# Valmar.net
KiCad netlist of a schematic drawn in EasyEDA Pro
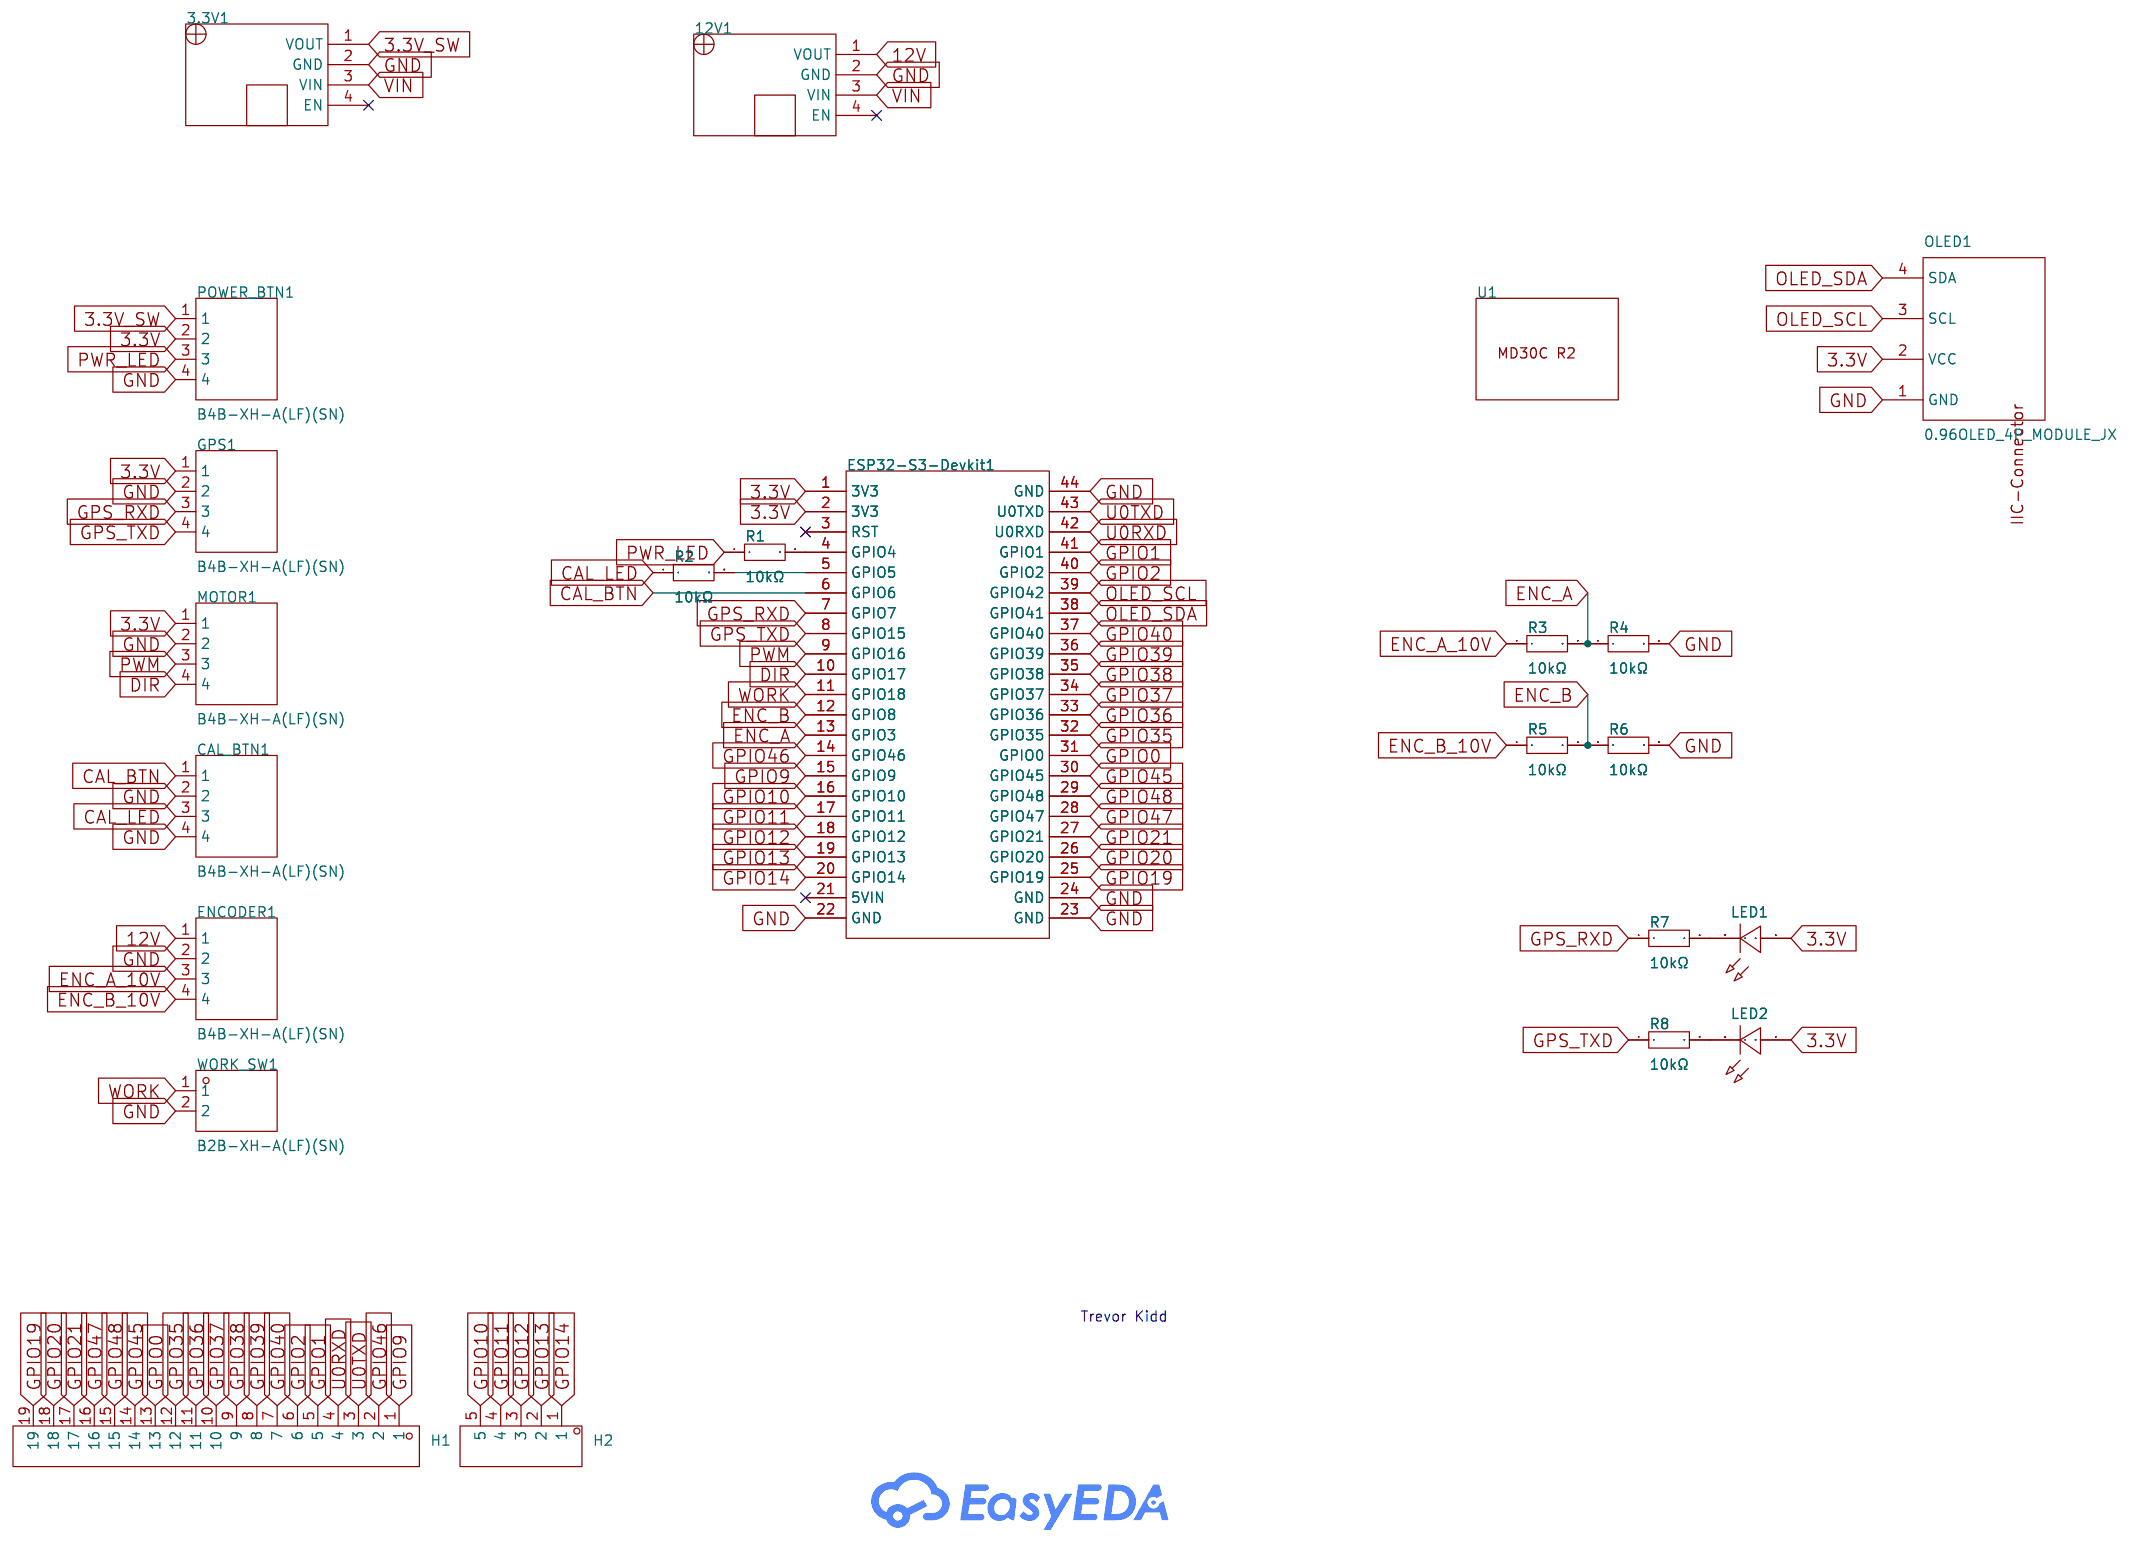
[diagram p0: schematic sheet]

(export (version "E")
  (design (tool "Eeschema 10.0.6"))
  (components
    (comp (ref "3.3V1")
      (value "~")
      (footprint "easyedapro:Power Module")
      (libsource (lib "easyedapro") (part "Power Module"))
    )
    (comp (ref "12V1")
      (value "~")
      (footprint "easyedapro:Power Module")
      (libsource (lib "easyedapro") (part "Power Module"))
    )
    (comp (ref "CAL_BTN1")
      (value "B4B-XH-A(LF)(SN)")
      (footprint "easyedapro:CONN-TH_B4B-XH-A-LF-SN")
      (fields (field (name "Manufacturer") "JST"))
      (libsource (lib "easyedapro") (part "B4B-XH-A(LF)(SN)"))
    )
    (comp (ref "ENCODER1")
      (value "B4B-XH-A(LF)(SN)")
      (footprint "easyedapro:CONN-TH_B4B-XH-A-LF-SN")
      (fields (field (name "Manufacturer") "JST"))
      (libsource (lib "easyedapro") (part "B4B-XH-A(LF)(SN)"))
    )
    (comp (ref "ESP32-S3-Devkit1")
      (value "~")
      (footprint "easyedapro:ESP32-S3-Devkit")
      (libsource (lib "easyedapro") (part "ESP32S3-Devkit"))
    )
    (comp (ref "GPS1")
      (value "B4B-XH-A(LF)(SN)")
      (footprint "easyedapro:CONN-TH_B4B-XH-A-LF-SN")
      (fields (field (name "Manufacturer") "JST"))
      (libsource (lib "easyedapro") (part "B4B-XH-A(LF)(SN)"))
    )
    (comp (ref "H1")
      (value "~")
      (footprint "easyedapro:HDR-TH_19P-P2.54-V-M")
      (libsource (lib "easyedapro") (part "HDR_2.54-1x19P"))
    )
    (comp (ref "H2")
      (value "~")
      (footprint "easyedapro:HDR-TH_5P-P2.54-V-M")
      (libsource (lib "easyedapro") (part "MTP125-1105S1"))
    )
    (comp (ref "LED1")
      (value "~")
      (footprint "easyedapro:LED-TH_BD3.8-P2.54-FD_BLUE")
      (libsource (lib "easyedapro") (part "LED_TH-B"))
    )
    (comp (ref "LED2")
      (value "~")
      (footprint "easyedapro:LED-TH_BD3.8-P2.54-FD_BLUE")
      (libsource (lib "easyedapro") (part "LED_TH-B"))
    )
    (comp (ref "MOTOR1")
      (value "B4B-XH-A(LF)(SN)")
      (footprint "easyedapro:CONN-TH_B4B-XH-A-LF-SN")
      (fields (field (name "Manufacturer") "JST"))
      (libsource (lib "easyedapro") (part "B4B-XH-A(LF)(SN)"))
    )
    (comp (ref "OLED1")
      (value "0.96OLED_4P_MODULE_JX")
      (footprint "easyedapro:0.96OLED_4P")
      (libsource (lib "easyedapro") (part "0.96OLED_4P_MODULE_JX"))
    )
    (comp (ref "POWER_BTN1")
      (value "B4B-XH-A(LF)(SN)")
      (footprint "easyedapro:CONN-TH_B4B-XH-A-LF-SN")
      (fields (field (name "Manufacturer") "JST"))
      (libsource (lib "easyedapro") (part "B4B-XH-A(LF)(SN)"))
    )
    (comp (ref "R1")
      (value "10kΩ")
      (footprint "easyedapro:RES-TH_BD1.8-L3.2-P7.20-D0.4")
      (libsource (lib "easyedapro") (part "Res"))
    )
    (comp (ref "R2")
      (value "10kΩ")
      (footprint "easyedapro:RES-TH_BD1.8-L3.2-P7.20-D0.4")
      (libsource (lib "easyedapro") (part "Res"))
    )
    (comp (ref "R3")
      (value "10kΩ")
      (footprint "easyedapro:RES-TH_BD1.8-L3.2-P7.20-D0.4")
      (libsource (lib "easyedapro") (part "Res"))
    )
    (comp (ref "R4")
      (value "10kΩ")
      (footprint "easyedapro:RES-TH_BD1.8-L3.2-P7.20-D0.4")
      (libsource (lib "easyedapro") (part "Res"))
    )
    (comp (ref "R5")
      (value "10kΩ")
      (footprint "easyedapro:RES-TH_BD1.8-L3.2-P7.20-D0.4")
      (libsource (lib "easyedapro") (part "Res"))
    )
    (comp (ref "R6")
      (value "10kΩ")
      (footprint "easyedapro:RES-TH_BD1.8-L3.2-P7.20-D0.4")
      (libsource (lib "easyedapro") (part "Res"))
    )
    (comp (ref "R7")
      (value "10kΩ")
      (footprint "easyedapro:RES-TH_BD1.8-L3.2-P7.20-D0.4")
      (libsource (lib "easyedapro") (part "Res"))
    )
    (comp (ref "R8")
      (value "10kΩ")
      (footprint "easyedapro:RES-TH_BD1.8-L3.2-P7.20-D0.4")
      (libsource (lib "easyedapro") (part "Res"))
    )
    (comp (ref "U1")
      (value "~")
      (footprint "easyedapro:MD30C R2")
      (libsource (lib "easyedapro") (part "MD30C R2"))
    )
    (comp (ref "WORK_SW1")
      (value "B2B-XH-A(LF)(SN)")
      (footprint "easyedapro:CONN-TH_B2B-XH-A-LF-SN")
      (fields (field (name "Manufacturer") "JST"))
      (libsource (lib "easyedapro") (part "B2B-XH-A (LF)(SN)"))
    )
  )
  (nets
    (net (code "1") (name "3.3V") (class "Default")
      (node (ref "ESP32-S3-Devkit1") (pin "1") (pinfunction "3V3_1") (pintype "input"))
      (node (ref "ESP32-S3-Devkit1") (pin "2") (pinfunction "3V3_2") (pintype "input"))
      (node (ref "GPS1") (pin "1") (pinfunction "1_1") (pintype "unspecified"))
      (node (ref "LED1") (pin "1") (pinfunction "C_1") (pintype "input"))
      (node (ref "LED2") (pin "1") (pinfunction "C_1") (pintype "input"))
      (node (ref "MOTOR1") (pin "1") (pinfunction "1_1") (pintype "unspecified"))
      (node (ref "OLED1") (pin "2") (pinfunction "VCC_2") (pintype "unspecified"))
      (node (ref "POWER_BTN1") (pin "2") (pinfunction "2_2") (pintype "unspecified"))
    )
    (net (code "2") (name "3.3V_SW") (class "Default")
      (node (ref "3.3V1") (pin "1") (pinfunction "VOUT_1") (pintype "input"))
      (node (ref "POWER_BTN1") (pin "1") (pinfunction "1_1") (pintype "unspecified"))
    )
    (net (code "3") (name "12V") (class "Default")
      (node (ref "12V1") (pin "1") (pinfunction "VOUT_1") (pintype "input"))
      (node (ref "ENCODER1") (pin "1") (pinfunction "1_1") (pintype "unspecified"))
    )
    (net (code "4") (name "CAL_BTN") (class "Default")
      (node (ref "CAL_BTN1") (pin "1") (pinfunction "1_1") (pintype "unspecified"))
      (node (ref "ESP32-S3-Devkit1") (pin "6") (pinfunction "GPIO6_6") (pintype "input"))
    )
    (net (code "5") (name "CAL_LED") (class "Default")
      (node (ref "CAL_BTN1") (pin "3") (pinfunction "3_3") (pintype "unspecified"))
      (node (ref "R2") (pin "1") (pinfunction "1_1") (pintype "input"))
    )
    (net (code "6") (name "DIR") (class "Default")
      (node (ref "ESP32-S3-Devkit1") (pin "10") (pinfunction "GPIO17_10") (pintype "input"))
      (node (ref "MOTOR1") (pin "4") (pinfunction "4_4") (pintype "unspecified"))
    )
    (net (code "7") (name "ENC_A") (class "Default")
      (node (ref "ESP32-S3-Devkit1") (pin "13") (pinfunction "GPIO3_13") (pintype "input"))
      (node (ref "R3") (pin "2") (pinfunction "2_2") (pintype "input"))
      (node (ref "R4") (pin "1") (pinfunction "1_1") (pintype "input"))
    )
    (net (code "8") (name "ENC_A_10V") (class "Default")
      (node (ref "ENCODER1") (pin "3") (pinfunction "3_3") (pintype "unspecified"))
      (node (ref "R3") (pin "1") (pinfunction "1_1") (pintype "input"))
    )
    (net (code "9") (name "ENC_B") (class "Default")
      (node (ref "ESP32-S3-Devkit1") (pin "12") (pinfunction "GPIO8_12") (pintype "input"))
      (node (ref "R5") (pin "2") (pinfunction "2_2") (pintype "input"))
      (node (ref "R6") (pin "1") (pinfunction "1_1") (pintype "input"))
    )
    (net (code "10") (name "ENC_B_10V") (class "Default")
      (node (ref "ENCODER1") (pin "4") (pinfunction "4_4") (pintype "unspecified"))
      (node (ref "R5") (pin "1") (pinfunction "1_1") (pintype "input"))
    )
    (net (code "11") (name "GND") (class "Default")
      (node (ref "12V1") (pin "2") (pinfunction "GND_2") (pintype "input"))
      (node (ref "3.3V1") (pin "2") (pinfunction "GND_2") (pintype "input"))
      (node (ref "CAL_BTN1") (pin "2") (pinfunction "2_2") (pintype "unspecified"))
      (node (ref "CAL_BTN1") (pin "4") (pinfunction "4_4") (pintype "unspecified"))
      (node (ref "ENCODER1") (pin "2") (pinfunction "2_2") (pintype "unspecified"))
      (node (ref "ESP32-S3-Devkit1") (pin "22") (pinfunction "GND_22") (pintype "input"))
      (node (ref "ESP32-S3-Devkit1") (pin "23") (pinfunction "GND_23") (pintype "input"))
      (node (ref "ESP32-S3-Devkit1") (pin "24") (pinfunction "GND_24") (pintype "input"))
      (node (ref "ESP32-S3-Devkit1") (pin "44") (pinfunction "GND_44") (pintype "input"))
      (node (ref "GPS1") (pin "2") (pinfunction "2_2") (pintype "unspecified"))
      (node (ref "MOTOR1") (pin "2") (pinfunction "2_2") (pintype "unspecified"))
      (node (ref "OLED1") (pin "1") (pinfunction "GND_1") (pintype "unspecified"))
      (node (ref "POWER_BTN1") (pin "4") (pinfunction "4_4") (pintype "unspecified"))
      (node (ref "R4") (pin "2") (pinfunction "2_2") (pintype "input"))
      (node (ref "R6") (pin "2") (pinfunction "2_2") (pintype "input"))
      (node (ref "WORK_SW1") (pin "2") (pinfunction "2_2") (pintype "unspecified"))
    )
    (net (code "12") (name "GPIO0") (class "Default")
      (node (ref "ESP32-S3-Devkit1") (pin "31") (pinfunction "GPIO0_31") (pintype "input"))
      (node (ref "H1") (pin "13") (pinfunction "13_13") (pintype "input"))
    )
    (net (code "13") (name "GPIO1") (class "Default")
      (node (ref "ESP32-S3-Devkit1") (pin "41") (pinfunction "GPIO1_41") (pintype "input"))
      (node (ref "H1") (pin "5") (pinfunction "5_5") (pintype "input"))
    )
    (net (code "14") (name "GPIO2") (class "Default")
      (node (ref "ESP32-S3-Devkit1") (pin "40") (pinfunction "GPIO2_40") (pintype "input"))
      (node (ref "H1") (pin "6") (pinfunction "6_6") (pintype "input"))
    )
    (net (code "15") (name "GPIO9") (class "Default")
      (node (ref "ESP32-S3-Devkit1") (pin "15") (pinfunction "GPIO9_15") (pintype "input"))
      (node (ref "H1") (pin "1") (pinfunction "1_1") (pintype "input"))
    )
    (net (code "16") (name "GPIO10") (class "Default")
      (node (ref "ESP32-S3-Devkit1") (pin "16") (pinfunction "GPIO10_16") (pintype "input"))
      (node (ref "H2") (pin "5") (pinfunction "5_5") (pintype "input"))
    )
    (net (code "17") (name "GPIO11") (class "Default")
      (node (ref "ESP32-S3-Devkit1") (pin "17") (pinfunction "GPIO11_17") (pintype "input"))
      (node (ref "H2") (pin "4") (pinfunction "4_4") (pintype "input"))
    )
    (net (code "18") (name "GPIO12") (class "Default")
      (node (ref "ESP32-S3-Devkit1") (pin "18") (pinfunction "GPIO12_18") (pintype "input"))
      (node (ref "H2") (pin "3") (pinfunction "3_3") (pintype "input"))
    )
    (net (code "19") (name "GPIO13") (class "Default")
      (node (ref "ESP32-S3-Devkit1") (pin "19") (pinfunction "GPIO13_19") (pintype "input"))
      (node (ref "H2") (pin "2") (pinfunction "2_2") (pintype "input"))
    )
    (net (code "20") (name "GPIO14") (class "Default")
      (node (ref "ESP32-S3-Devkit1") (pin "20") (pinfunction "GPIO14_20") (pintype "input"))
      (node (ref "H2") (pin "1") (pinfunction "1_1") (pintype "input"))
    )
    (net (code "21") (name "GPIO19") (class "Default")
      (node (ref "ESP32-S3-Devkit1") (pin "25") (pinfunction "GPIO19_25") (pintype "input"))
      (node (ref "H1") (pin "19") (pinfunction "19_19") (pintype "input"))
    )
    (net (code "22") (name "GPIO20") (class "Default")
      (node (ref "ESP32-S3-Devkit1") (pin "26") (pinfunction "GPIO20_26") (pintype "input"))
      (node (ref "H1") (pin "18") (pinfunction "18_18") (pintype "input"))
    )
    (net (code "23") (name "GPIO21") (class "Default")
      (node (ref "ESP32-S3-Devkit1") (pin "27") (pinfunction "GPIO21_27") (pintype "input"))
      (node (ref "H1") (pin "17") (pinfunction "17_17") (pintype "input"))
    )
    (net (code "24") (name "GPIO35") (class "Default")
      (node (ref "ESP32-S3-Devkit1") (pin "32") (pinfunction "GPIO35_32") (pintype "input"))
      (node (ref "H1") (pin "12") (pinfunction "12_12") (pintype "input"))
    )
    (net (code "25") (name "GPIO36") (class "Default")
      (node (ref "ESP32-S3-Devkit1") (pin "33") (pinfunction "GPIO36_33") (pintype "input"))
      (node (ref "H1") (pin "11") (pinfunction "11_11") (pintype "input"))
    )
    (net (code "26") (name "GPIO37") (class "Default")
      (node (ref "ESP32-S3-Devkit1") (pin "34") (pinfunction "GPIO37_34") (pintype "input"))
      (node (ref "H1") (pin "10") (pinfunction "10_10") (pintype "input"))
    )
    (net (code "27") (name "GPIO38") (class "Default")
      (node (ref "ESP32-S3-Devkit1") (pin "35") (pinfunction "GPIO38_35") (pintype "input"))
      (node (ref "H1") (pin "9") (pinfunction "9_9") (pintype "input"))
    )
    (net (code "28") (name "GPIO39") (class "Default")
      (node (ref "ESP32-S3-Devkit1") (pin "36") (pinfunction "GPIO39_36") (pintype "input"))
      (node (ref "H1") (pin "8") (pinfunction "8_8") (pintype "input"))
    )
    (net (code "29") (name "GPIO40") (class "Default")
      (node (ref "ESP32-S3-Devkit1") (pin "37") (pinfunction "GPIO40_37") (pintype "input"))
      (node (ref "H1") (pin "7") (pinfunction "7_7") (pintype "input"))
    )
    (net (code "30") (name "GPIO45") (class "Default")
      (node (ref "ESP32-S3-Devkit1") (pin "30") (pinfunction "GPIO45_30") (pintype "input"))
      (node (ref "H1") (pin "14") (pinfunction "14_14") (pintype "input"))
    )
    (net (code "31") (name "GPIO46") (class "Default")
      (node (ref "ESP32-S3-Devkit1") (pin "14") (pinfunction "GPIO46_14") (pintype "input"))
      (node (ref "H1") (pin "2") (pinfunction "2_2") (pintype "input"))
    )
    (net (code "32") (name "GPIO47") (class "Default")
      (node (ref "ESP32-S3-Devkit1") (pin "28") (pinfunction "GPIO47_28") (pintype "input"))
      (node (ref "H1") (pin "16") (pinfunction "16_16") (pintype "input"))
    )
    (net (code "33") (name "GPIO48") (class "Default")
      (node (ref "ESP32-S3-Devkit1") (pin "29") (pinfunction "GPIO48_29") (pintype "input"))
      (node (ref "H1") (pin "15") (pinfunction "15_15") (pintype "input"))
    )
    (net (code "34") (name "GPS_RXD") (class "Default")
      (node (ref "ESP32-S3-Devkit1") (pin "7") (pinfunction "GPIO7_7") (pintype "input"))
      (node (ref "GPS1") (pin "3") (pinfunction "3_3") (pintype "unspecified"))
      (node (ref "R7") (pin "1") (pinfunction "1_1") (pintype "input"))
    )
    (net (code "35") (name "GPS_TXD") (class "Default")
      (node (ref "ESP32-S3-Devkit1") (pin "8") (pinfunction "GPIO15_8") (pintype "input"))
      (node (ref "GPS1") (pin "4") (pinfunction "4_4") (pintype "unspecified"))
      (node (ref "R8") (pin "1") (pinfunction "1_1") (pintype "input"))
    )
    (net (code "36") (name "Net-(ESP32-S3-Devkit1-GPIO4)") (class "Default")
      (node (ref "ESP32-S3-Devkit1") (pin "4") (pinfunction "GPIO4_4") (pintype "input"))
      (node (ref "R1") (pin "2") (pinfunction "2_2") (pintype "input"))
    )
    (net (code "37") (name "Net-(ESP32-S3-Devkit1-GPIO5)") (class "Default")
      (node (ref "ESP32-S3-Devkit1") (pin "5") (pinfunction "GPIO5_5") (pintype "input"))
      (node (ref "R2") (pin "2") (pinfunction "2_2") (pintype "input"))
    )
    (net (code "38") (name "Net-(LED1-A)") (class "Default")
      (node (ref "LED1") (pin "2") (pinfunction "A_2") (pintype "input"))
      (node (ref "R7") (pin "2") (pinfunction "2_2") (pintype "input"))
    )
    (net (code "39") (name "Net-(LED2-A)") (class "Default")
      (node (ref "LED2") (pin "2") (pinfunction "A_2") (pintype "input"))
      (node (ref "R8") (pin "2") (pinfunction "2_2") (pintype "input"))
    )
    (net (code "40") (name "OLED_SCL") (class "Default")
      (node (ref "ESP32-S3-Devkit1") (pin "39") (pinfunction "GPIO42_39") (pintype "input"))
      (node (ref "OLED1") (pin "3") (pinfunction "SCL_3") (pintype "unspecified"))
    )
    (net (code "41") (name "OLED_SDA") (class "Default")
      (node (ref "ESP32-S3-Devkit1") (pin "38") (pinfunction "GPIO41_38") (pintype "input"))
      (node (ref "OLED1") (pin "4") (pinfunction "SDA_4") (pintype "unspecified"))
    )
    (net (code "42") (name "PWM") (class "Default")
      (node (ref "ESP32-S3-Devkit1") (pin "9") (pinfunction "GPIO16_9") (pintype "input"))
      (node (ref "MOTOR1") (pin "3") (pinfunction "3_3") (pintype "unspecified"))
    )
    (net (code "43") (name "PWR_LED") (class "Default")
      (node (ref "POWER_BTN1") (pin "3") (pinfunction "3_3") (pintype "unspecified"))
      (node (ref "R1") (pin "1") (pinfunction "1_1") (pintype "input"))
    )
    (net (code "44") (name "U0RXD") (class "Default")
      (node (ref "ESP32-S3-Devkit1") (pin "42") (pinfunction "U0RXD_42") (pintype "input"))
      (node (ref "H1") (pin "4") (pinfunction "4_4") (pintype "input"))
    )
    (net (code "45") (name "U0TXD") (class "Default")
      (node (ref "ESP32-S3-Devkit1") (pin "43") (pinfunction "U0TXD_43") (pintype "input"))
      (node (ref "H1") (pin "3") (pinfunction "3_3") (pintype "input"))
    )
    (net (code "46") (name "VIN") (class "Default")
      (node (ref "12V1") (pin "3") (pinfunction "VIN_3") (pintype "input"))
      (node (ref "3.3V1") (pin "3") (pinfunction "VIN_3") (pintype "input"))
    )
    (net (code "47") (name "WORK") (class "Default")
      (node (ref "ESP32-S3-Devkit1") (pin "11") (pinfunction "GPIO18_11") (pintype "input"))
      (node (ref "WORK_SW1") (pin "1") (pinfunction "1_1") (pintype "unspecified"))
    )
    (net (code "48") (name "unconnected-(3.3V1-EN-Pad4)") (class "Default")
      (node (ref "3.3V1") (pin "4") (pinfunction "EN_4") (pintype "input+no_connect"))
    )
    (net (code "49") (name "unconnected-(12V1-EN-Pad4)") (class "Default")
      (node (ref "12V1") (pin "4") (pinfunction "EN_4") (pintype "input+no_connect"))
    )
    (net (code "50") (name "unconnected-(ESP32-S3-Devkit1-5VIN-Pad21)") (class "Default")
      (node (ref "ESP32-S3-Devkit1") (pin "21") (pinfunction "5VIN_21") (pintype "input+no_connect"))
    )
    (net (code "51") (name "unconnected-(ESP32-S3-Devkit1-RST-Pad3)") (class "Default")
      (node (ref "ESP32-S3-Devkit1") (pin "3") (pinfunction "RST_3") (pintype "input+no_connect"))
    )
  )
)
